# Power.net
KiCad netlist of a schematic drawn in Altium Designer
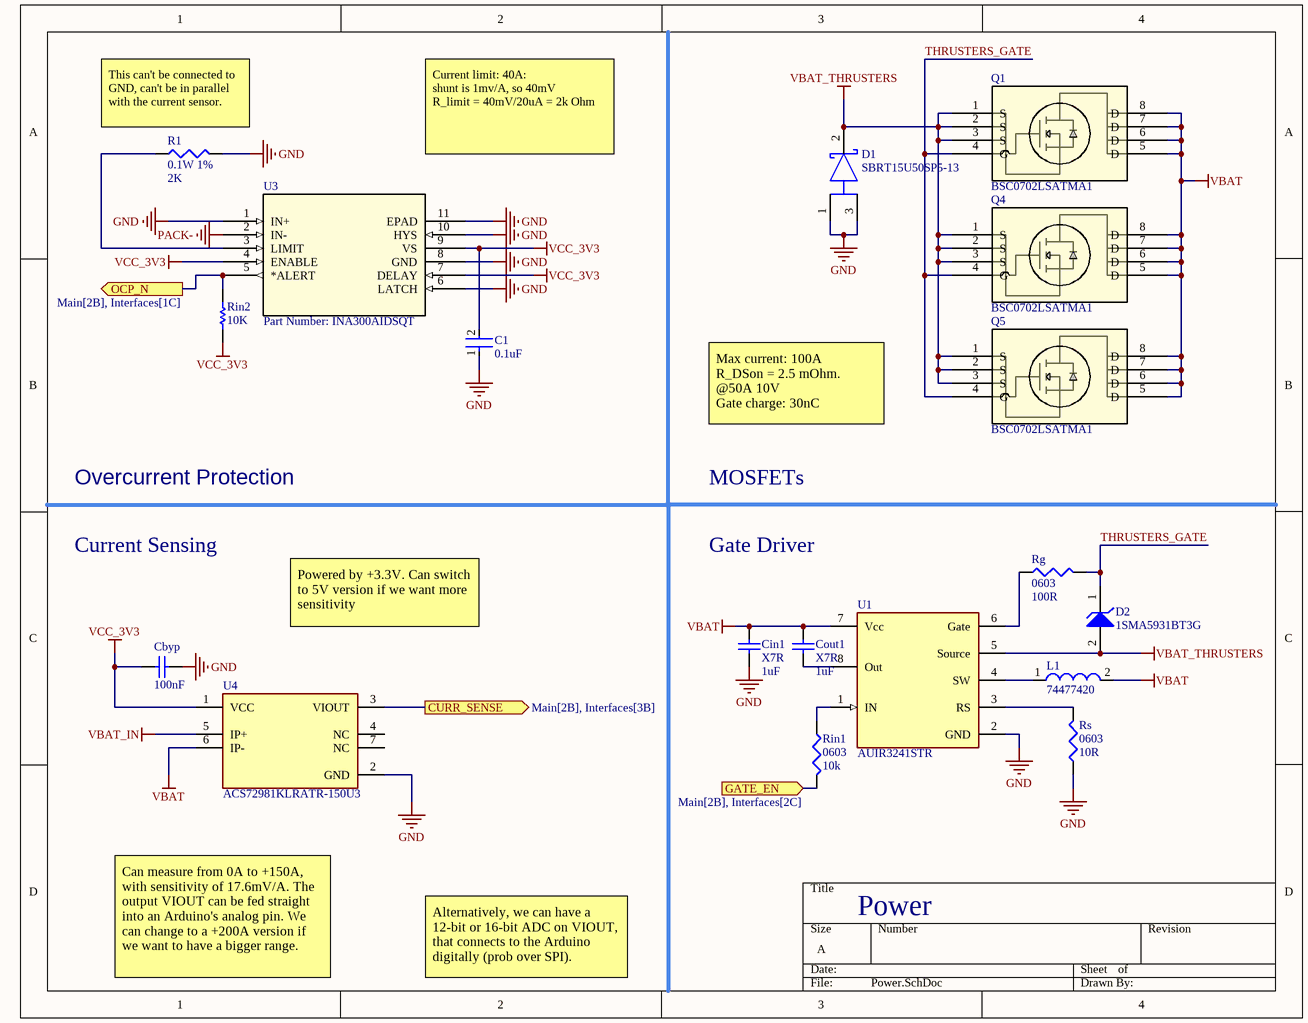
[diagram p0: Power.SchDoc]

(export (version "E")
  (design (tool "Eeschema 10.0.6"))
  (components
    (comp (ref "C1")
      (value "0.1uF")
      (footprint "FP-C0603C-CF-MFG")
      (description "CAP CER 0.1UF 10V X7R 0603")
      (fields (field (name "TOLERANCE") "0.1") (field (name "MANUFACTURER PART NUMBER") "C0603C104K8RACTU"))
      (libsource (lib "Altium Content Vault") (part "b4654b650e69147ec39a6b967a45e02"))
    )
    (comp (ref "Cbyp")
      (value "100nF")
      (footprint "Tauv-Lib:0603")
      (description "Capacitor")
      (libsource (lib "Simulation Generic Components") (part "Capacitor"))
    )
    (comp (ref "Cin1")
      (value "X7R")
      (footprint "C0805")
      (description "Capacitor")
      (fields (field (name "ALTIUM_VALUE") "1uF") (field (name "PUBLISHER") "Altium Limited"))
      (libsource (lib "Miscellaneous Devices") (part "Cap"))
    )
    (comp (ref "Cout1")
      (value "X7R")
      (footprint "C0805")
      (description "Capacitor")
      (fields (field (name "ALTIUM_VALUE") "1uF") (field (name "PUBLISHER") "Altium Limited"))
      (libsource (lib "Miscellaneous Devices") (part "Cap"))
    )
    (comp (ref "D1")
      (value "SBRT15U50SP5-13")
      (footprint "FP-PowerDI5-MFG")
      (description "50V 15A Rectifier Schottky Diode")
      (fields
        (field (name "OCTOPART") "https://octopart.com/pds3200-13-diodes+inc.-332544")
        (field (name "MANUFACTURER") "Diodes Inc.")
      )
      (libsource (lib "Altium Content Vault") (part "0222f6c3f9f8f3c07decc49f824026a"))
    )
    (comp (ref "D2")
      (value "1SMA5931BT3G")
      (footprint "ONSC-SMA-2-403D-02_F_V")
      (description "1.5 W Zener Voltage Regulator, 2-Pin SMA, Pb-Free, Tape and Reel")
      (fields (field (name "MANUFACTURER") "On Semiconductor"))
      (libsource (lib "Altium Content Vault") (part "ONSC-K1A2-2"))
    )
    (comp (ref "L1")
      (value "74477420")
      (footprint "WE-PD2-M")
      (description "SMD Power Inductor WE-PD2, L = 100 µH")
      (libsource (lib "Altium Content Vault") (part "PAS-IND-INDUCTOR-2"))
    )
    (comp (ref "Q1")
      (value "BSC0702LSATMA1")
      (footprint "PG-TDSON-8-7")
      (description "No Description Available")
      (libsource (lib "TAUV-Lib") (part "BSC0702LSATMA1"))
    )
    (comp (ref "Q4")
      (value "BSC0702LSATMA1")
      (footprint "PG-TDSON-8-7")
      (description "No Description Available")
      (libsource (lib "TAUV-Lib") (part "BSC0702LSATMA1"))
    )
    (comp (ref "Q5")
      (value "BSC0702LSATMA1")
      (footprint "PG-TDSON-8-7")
      (description "No Description Available")
      (libsource (lib "TAUV-Lib") (part "BSC0702LSATMA1"))
    )
    (comp (ref "R1")
      (value "0.1W 1%")
      (footprint "J1-0603")
      (description "2k 0.1W 1%")
      (fields (field (name "ALTIUM_VALUE") "2K") (field (name "PUBLISHER") "Altium Limited"))
      (libsource (lib "Miscellaneous Devices") (part "Res3"))
    )
    (comp (ref "Rg")
      (value "0603")
      (footprint "J1-0603")
      (description "Resistor")
      (fields (field (name "ALTIUM_VALUE") "100R") (field (name "PUBLISHER") "Altium Limited"))
      (libsource (lib "Miscellaneous Devices") (part "Res3"))
    )
    (comp (ref "Rin1")
      (value "0603")
      (footprint "J1-0603")
      (description "Resistor")
      (fields (field (name "ALTIUM_VALUE") "10k") (field (name "PUBLISHER") "Altium Limited"))
      (libsource (lib "Miscellaneous Devices") (part "Res3"))
    )
    (comp (ref "Rin2")
      (value "10K")
      (footprint "RESC0603(1608)_N")
      (description "10K 0.1W 5% 0603 (1608 Metric)  SMD")
      (fields (field (name "TOLERANCE") "5 %") (field (name "POWER") "0.1 W"))
      (libsource (lib "Altium Content Vault") (part "RES"))
    )
    (comp (ref "Rs")
      (value "0603")
      (footprint "J1-0603")
      (description "Resistor")
      (fields (field (name "ALTIUM_VALUE") "10R") (field (name "PUBLISHER") "Altium Limited"))
      (libsource (lib "Miscellaneous Devices") (part "Res3"))
    )
    (comp (ref "U1")
      (value "AUIR3241STR")
      (footprint "FP-PG-DSO-8-MFG")
      (description "IC GATE DRVR HIGH-SIDE 8SO")
      (libsource (lib "Altium Content Vault") (part "34ae5cb6024c322bdcbf0313f74d293"))
    )
    (comp (ref "U3")
      (value "Part Number: INA300AIDSQT")
      (footprint "DSQ10_P9X1P5")
      (description "No Description Available")
      (fields
        (field (name "MANUFACTURER_PART_NUMBER") "INA300AIDSQT")
        (field (name "COPYRIGHT") "Copyright (C) 2018 Accelerated Designs. All rights reserved")
      )
      (libsource (lib "Tauv-Lib") (part "INA300AIDSQT"))
    )
    (comp (ref "U4")
      (value "ACS72981KLRATR-150U3")
      (footprint "FP-LR-7-MFG")
      (description "HIGH PRECISION LINEAR HALL EFFEC")
      (libsource (lib "Altium Content Vault") (part "5dc6678e74109c55151fc4d560803b8"))
    )
  )
  (nets
    (net (code "1") (name "/CURR_SENSE") (class "Default")
      (node (ref "U4") (pin "3") (pinfunction "VIOUT_3") (pintype "passive"))
    )
    (net (code "2") (name "/GATE_EN") (class "Default")
      (node (ref "Rin1") (pin "2") (pinfunction "2_2") (pintype "passive"))
    )
    (net (code "3") (name "/OCP_N") (class "Default")
      (node (ref "Rin2") (pin "1") (pinfunction "1_1") (pintype "passive"))
      (node (ref "U3") (pin "5") (pinfunction "*ALERT_5") (pintype "output"))
    )
    (net (code "4") (name "/THRUSTERS_GATE") (class "Default")
      (node (ref "D2") (pin "1") (pinfunction "K_1") (pintype "passive"))
      (node (ref "Q1") (pin "4") (pinfunction "G_4") (pintype "passive"))
      (node (ref "Q4") (pin "4") (pinfunction "G_4") (pintype "passive"))
      (node (ref "Q5") (pin "4") (pinfunction "G_4") (pintype "passive"))
      (node (ref "Rg") (pin "2") (pinfunction "2_2") (pintype "passive"))
    )
    (net (code "5") (name "GND") (class "Default")
      (node (ref "C1") (pin "1") (pinfunction "1_1") (pintype "passive"))
      (node (ref "Cbyp") (pin "2") (pinfunction "2_2") (pintype "passive"))
      (node (ref "Cin1") (pin "1") (pinfunction "1_1") (pintype "passive"))
      (node (ref "D1") (pin "1") (pinfunction "A_1") (pintype "passive"))
      (node (ref "D1") (pin "3") (pinfunction "A_3") (pintype "passive"))
      (node (ref "R1") (pin "2") (pinfunction "2_2") (pintype "passive"))
      (node (ref "Rs") (pin "1") (pinfunction "1_1") (pintype "passive"))
      (node (ref "U1") (pin "2") (pinfunction "GND_2") (pintype "power_in"))
      (node (ref "U3") (pin "1") (pinfunction "IN+_1") (pintype "input"))
      (node (ref "U3") (pin "10") (pinfunction "HYS_10") (pintype "input"))
      (node (ref "U3") (pin "11") (pinfunction "EPAD_11") (pintype "passive"))
      (node (ref "U3") (pin "6") (pinfunction "LATCH_6") (pintype "input"))
      (node (ref "U3") (pin "8") (pinfunction "GND_8") (pintype "power_in"))
      (node (ref "U4") (pin "2") (pinfunction "GND_2") (pintype "power_in"))
    )
    (net (code "6") (name "Net-(U1-Gate)") (class "Default")
      (node (ref "Rg") (pin "1") (pinfunction "1_1") (pintype "passive"))
      (node (ref "U1") (pin "6") (pinfunction "Gate_6") (pintype "passive"))
    )
    (net (code "7") (name "Net-(U1-IN)") (class "Default")
      (node (ref "Rin1") (pin "1") (pinfunction "1_1") (pintype "passive"))
      (node (ref "U1") (pin "1") (pinfunction "IN_1") (pintype "input"))
    )
    (net (code "8") (name "Net-(U1-Out)") (class "Default")
      (node (ref "Cout1") (pin "1") (pinfunction "1_1") (pintype "passive"))
      (node (ref "U1") (pin "8") (pinfunction "Out_8") (pintype "passive"))
    )
    (net (code "9") (name "Net-(U1-RS)") (class "Default")
      (node (ref "Rs") (pin "2") (pinfunction "2_2") (pintype "passive"))
      (node (ref "U1") (pin "3") (pinfunction "RS_3") (pintype "passive"))
    )
    (net (code "10") (name "Net-(U1-SW)") (class "Default")
      (node (ref "L1") (pin "1") (pinfunction "1_1") (pintype "passive"))
      (node (ref "U1") (pin "4") (pinfunction "SW_4") (pintype "passive"))
    )
    (net (code "11") (name "Net-(U3-LIMIT)") (class "Default")
      (node (ref "R1") (pin "1") (pinfunction "1_1") (pintype "passive"))
      (node (ref "U3") (pin "3") (pinfunction "LIMIT_3") (pintype "input"))
    )
    (net (code "12") (name "PACK-") (class "Default")
      (node (ref "U3") (pin "2") (pinfunction "IN-_2") (pintype "input"))
    )
    (net (code "13") (name "VBAT") (class "Default")
      (node (ref "Cin1") (pin "2") (pinfunction "2_2") (pintype "passive"))
      (node (ref "Cout1") (pin "2") (pinfunction "2_2") (pintype "passive"))
      (node (ref "L1") (pin "2") (pinfunction "2_2") (pintype "passive"))
      (node (ref "Q1") (pin "5") (pinfunction "D_5") (pintype "passive"))
      (node (ref "Q1") (pin "6") (pinfunction "D_6") (pintype "passive"))
      (node (ref "Q1") (pin "7") (pinfunction "D_7") (pintype "passive"))
      (node (ref "Q1") (pin "8") (pinfunction "D_8") (pintype "passive"))
      (node (ref "Q4") (pin "5") (pinfunction "D_5") (pintype "passive"))
      (node (ref "Q4") (pin "6") (pinfunction "D_6") (pintype "passive"))
      (node (ref "Q4") (pin "7") (pinfunction "D_7") (pintype "passive"))
      (node (ref "Q4") (pin "8") (pinfunction "D_8") (pintype "passive"))
      (node (ref "Q5") (pin "5") (pinfunction "D_5") (pintype "passive"))
      (node (ref "Q5") (pin "6") (pinfunction "D_6") (pintype "passive"))
      (node (ref "Q5") (pin "7") (pinfunction "D_7") (pintype "passive"))
      (node (ref "Q5") (pin "8") (pinfunction "D_8") (pintype "passive"))
      (node (ref "U1") (pin "7") (pinfunction "Vcc_7") (pintype "power_in"))
      (node (ref "U4") (pin "6") (pinfunction "IP-_6") (pintype "passive"))
    )
    (net (code "14") (name "VBAT_IN") (class "Default")
      (node (ref "U4") (pin "5") (pinfunction "IP+_5") (pintype "passive"))
    )
    (net (code "15") (name "VBAT_THRUSTERS") (class "Default")
      (node (ref "D1") (pin "2") (pinfunction "C_2") (pintype "passive"))
      (node (ref "D2") (pin "2") (pinfunction "A_2") (pintype "passive"))
      (node (ref "Q1") (pin "1") (pinfunction "S_1") (pintype "passive"))
      (node (ref "Q1") (pin "2") (pinfunction "S_2") (pintype "passive"))
      (node (ref "Q1") (pin "3") (pinfunction "S_3") (pintype "passive"))
      (node (ref "Q4") (pin "1") (pinfunction "S_1") (pintype "passive"))
      (node (ref "Q4") (pin "2") (pinfunction "S_2") (pintype "passive"))
      (node (ref "Q4") (pin "3") (pinfunction "S_3") (pintype "passive"))
      (node (ref "Q5") (pin "1") (pinfunction "S_1") (pintype "passive"))
      (node (ref "Q5") (pin "2") (pinfunction "S_2") (pintype "passive"))
      (node (ref "Q5") (pin "3") (pinfunction "S_3") (pintype "passive"))
      (node (ref "U1") (pin "5") (pinfunction "Source_5") (pintype "passive"))
    )
    (net (code "16") (name "VCC_3V3") (class "Default")
      (node (ref "C1") (pin "2") (pinfunction "2_2") (pintype "passive"))
      (node (ref "Cbyp") (pin "1") (pinfunction "1_1") (pintype "passive"))
      (node (ref "Rin2") (pin "2") (pinfunction "2_2") (pintype "passive"))
      (node (ref "U3") (pin "4") (pinfunction "ENABLE_4") (pintype "input"))
      (node (ref "U3") (pin "7") (pinfunction "DELAY_7") (pintype "input"))
      (node (ref "U3") (pin "9") (pinfunction "VS_9") (pintype "power_in"))
      (node (ref "U4") (pin "1") (pinfunction "VCC_1") (pintype "power_in"))
    )
    (net (code "17") (name "unconnected-(U4-NC-Pad4)") (class "Default")
      (node (ref "U4") (pin "4") (pinfunction "NC_4") (pintype "passive"))
    )
    (net (code "18") (name "unconnected-(U4-NC-Pad7)") (class "Default")
      (node (ref "U4") (pin "7") (pinfunction "NC_7") (pintype "passive"))
    )
  )
)
